# Ethylene_Sensor.net
KiCad netlist of a schematic drawn in Altium Designer
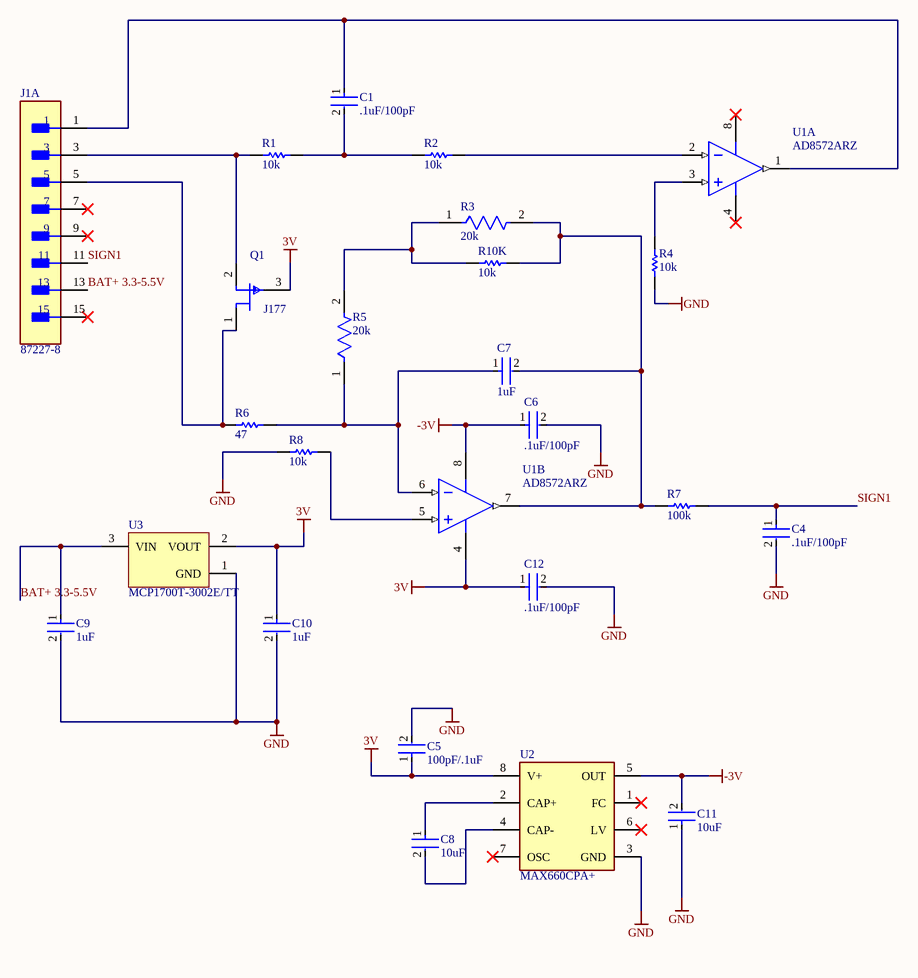
[diagram p0: Ethylene Sensor.SchDoc]

(export (version "E")
  (design (tool "Eeschema 10.0.6"))
  (components
    (comp (ref "C1")
      (value ".1uF/100pF")
      (footprint "FP-RCE0K1-MFG")
      (description "Cap Ceramic 100pF 100V C0G ±5% Radial 5mm +125°C Automotive Bulk")
      (fields (field (name "TOLERANCE") "5%"))
      (libsource (lib "Altium Content Vault") (part "b4654b650e69147ec39a6b967a45e02"))
    )
    (comp (ref "C4")
      (value ".1uF/100pF")
      (footprint "FP-RCE0K1-MFG")
      (description "Cap Ceramic 100pF 100V C0G ±5% Radial 5mm +125°C Automotive Bulk")
      (fields (field (name "TOLERANCE") "5%"))
      (libsource (lib "Altium Content Vault") (part "b4654b650e69147ec39a6b967a45e02"))
    )
    (comp (ref "C5")
      (value "100pF/.1uF")
      (footprint "FP-RCE0DB-MFG")
      (description "Cap Ceramic 100pF 100V C0G ±5% Radial 2.5mm +125°C Ammo Pack")
      (fields (field (name "TOLERANCE") "5%"))
      (libsource (lib "Altium Content Vault") (part "b4654b650e69147ec39a6b967a45e02"))
    )
    (comp (ref "C6")
      (value ".1uF/100pF")
      (footprint "FP-RCE0K1-MFG")
      (description "Cap Ceramic 100pF 100V C0G ±5% Radial 5mm +125°C Automotive Bulk")
      (fields (field (name "TOLERANCE") "5%"))
      (libsource (lib "Altium Content Vault") (part "b4654b650e69147ec39a6b967a45e02"))
    )
    (comp (ref "C7")
      (value "1uF")
      (footprint "FP-K105Z20Y5VF5TL2-MFG")
      (description "CAP CER 1UF 50V Y5V RADIAL")
      (fields
        (field (name "TOLERANCE") "-20+80%")
        (field (name "OCTOPART") "https://octopart.com/k105z20y5vf5tl2-vishay-39475252")
      )
      (libsource (lib "Altium Content Vault") (part "11868f565c42a9108669ba33697ecf6"))
    )
    (comp (ref "C8")
      (value "10uF")
      (footprint "FP-RCE3M1-MFG")
      (description "Cap Ceramic 10uF 25V X7R ±10% Radial 5mm +125°C Automotive Ammo Pack")
      (fields (field (name "TOLERANCE") "10%"))
      (libsource (lib "Altium Content Vault") (part "02cd4be3c70576c341d710602a673aa"))
    )
    (comp (ref "C9")
      (value "1uF")
      (footprint "FP-K105Z20Y5VF5TL2-MFG")
      (description "CAP CER 1UF 50V Y5V RADIAL")
      (fields
        (field (name "TOLERANCE") "-20+80%")
        (field (name "OCTOPART") "https://octopart.com/k105z20y5vf5tl2-vishay-39475252")
      )
      (libsource (lib "Altium Content Vault") (part "11868f565c42a9108669ba33697ecf6"))
    )
    (comp (ref "C10")
      (value "1uF")
      (footprint "FP-K105Z20Y5VF5TL2-MFG")
      (description "CAP CER 1UF 50V Y5V RADIAL")
      (fields
        (field (name "TOLERANCE") "-20+80%")
        (field (name "OCTOPART") "https://octopart.com/k105z20y5vf5tl2-vishay-39475252")
      )
      (libsource (lib "Altium Content Vault") (part "11868f565c42a9108669ba33697ecf6"))
    )
    (comp (ref "C11")
      (value "10uF")
      (footprint "FP-RCE3M1-MFG")
      (description "Cap Ceramic 10uF 25V X7R ±10% Radial 5mm +125°C Automotive Ammo Pack")
      (fields (field (name "TOLERANCE") "10%"))
      (libsource (lib "Altium Content Vault") (part "02cd4be3c70576c341d710602a673aa"))
    )
    (comp (ref "C12")
      (value ".1uF/100pF")
      (footprint "FP-RCE0K1-MFG")
      (description "Cap Ceramic 100pF 100V C0G ±5% Radial 5mm +125°C Automotive Bulk")
      (fields (field (name "TOLERANCE") "5%"))
      (libsource (lib "Altium Content Vault") (part "b4654b650e69147ec39a6b967a45e02"))
    )
    (comp (ref "J1")
      (value "87227-8")
      (footprint "FP-87227-8-MFG")
      (description "CONN HEADER VERT 16POS 2.54MM")
      (fields
        (field (name "MANUFACTURER") "TE Connectivity")
        (field (name "OCTOPART") "https://octopart.com/87227-8-te+connectivity-39407754")
      )
      (libsource (lib "Altium Content Vault") (part "4b6d22b45e2f925f038cba5d936fbcc"))
    )
    (comp (ref "Q1")
      (value "J177")
      (footprint "FP-318-08-IPC_C")
      (description "JFET P-CH 30V 0.225W SOT23")
      (libsource (lib "Altium Content Vault") (part "f35b6042eff1b6cb0a0a26375b7670e"))
    )
    (comp (ref "R1")
      (value "10k")
      (footprint "OMTE-RES7X2.5-2")
      (fields
        (field (name "TOLERANCE") "±5%")
        (field (name "PARTNUMBER") "OD103JE")
        (field (name "MANUFACTURER") "Ohmite")
      )
      (libsource (lib "Altium Content Vault") (part "RES-2"))
    )
    (comp (ref "R2")
      (value "10k")
      (footprint "OMTE-RES7X2.5-2")
      (fields
        (field (name "TOLERANCE") "±5%")
        (field (name "PARTNUMBER") "OD103JE")
        (field (name "MANUFACTURER") "Ohmite")
      )
      (libsource (lib "Altium Content Vault") (part "RES-2"))
    )
    (comp (ref "R3")
      (value "20k")
      (footprint "FP-S102K-MFG")
      (description "RES 20K OHM 0.6W 0.01% RADIAL")
      (fields (field (name "TOLERANCE") "0.01%"))
      (libsource (lib "Altium Content Vault") (part "1029c3af85768c4190bb7ad29bc67b5"))
    )
    (comp (ref "R4")
      (value "10k")
      (footprint "OMTE-RES7X2.5-2")
      (fields
        (field (name "TOLERANCE") "±5%")
        (field (name "PARTNUMBER") "OD103JE")
        (field (name "MANUFACTURER") "Ohmite")
      )
      (libsource (lib "Altium Content Vault") (part "RES-2"))
    )
    (comp (ref "R5")
      (value "20k")
      (footprint "FP-S102K-MFG")
      (description "RES 20K OHM 0.6W 0.01% RADIAL")
      (fields (field (name "TOLERANCE") "0.01%"))
      (libsource (lib "Altium Content Vault") (part "1029c3af85768c4190bb7ad29bc67b5"))
    )
    (comp (ref "R6")
      (value "47")
      (footprint "RESC1609X50X30LL10T20")
      (fields (field (name "MANUFACTURER") "Vishay Dale") (field (name "PART NUMBER") "CRCW060347R0FKEA"))
      (libsource (lib "Altium Content Vault") (part "RES"))
    )
    (comp (ref "R7")
      (value "100k")
      (footprint "RESA60-630X240")
      (description "Axial Resistor, 100 KOhm, +/- 1%, 0.25 W, -55 to 155 degC, 2-Pin THD, RoHS, Bulk")
      (fields (field (name "TOLERANCE") "1%"))
      (libsource (lib "Altium Content Vault") (part "RES-2"))
    )
    (comp (ref "R8")
      (value "10k")
      (footprint "OMTE-RES7X2.5-2")
      (fields
        (field (name "TOLERANCE") "±5%")
        (field (name "PARTNUMBER") "OD103JE")
        (field (name "MANUFACTURER") "Ohmite")
      )
      (libsource (lib "Altium Content Vault") (part "RES-2"))
    )
    (comp (ref "R10K")
      (value "10k")
      (footprint "OMTE-RES7X2.5-2")
      (fields
        (field (name "TOLERANCE") "±5%")
        (field (name "PARTNUMBER") "OD103JE")
        (field (name "MANUFACTURER") "Ohmite")
      )
      (libsource (lib "Altium Content Vault") (part "RES-2"))
    )
    (comp (ref "U1")
      (value "AD8572ARZ")
      (footprint "ADI-R-8_L")
      (fields (field (name "MANUFACTURER") "Analog Devices") (field (name "GENERIC PART NUMBER") "AD8572"))
      (libsource (lib "Altium Content Vault") (part "ADI-OP29X-R-8"))
    )
    (comp (ref "U2")
      (value "MAX660CPA+")
      (footprint "FP-P8-2-MFG")
      (description "IC REG CHARG PUMP INV 100MA 8DIP")
      (fields
        (field (name "OCTOPART") "https://octopart.com/max660cpa%2B-maxim+integrated-39427913")
        (field (name "MANUFACTURER") "Maxim Integrated")
      )
      (libsource (lib "Altium Content Vault") (part "cb4f88f8f8861f0afe4fdc40404f196"))
    )
    (comp (ref "U3")
      (value "MCP1700T-3002E/TT")
      (footprint "SOT-23-TT3_L")
      (description "Low Quiescent Current LDO, 3-Pin SOT-23, Extended Temperature, Tape and Reel")
      (libsource (lib "Altium Content Vault") (part "PM-LINEREG-MCP1700-IL3"))
    )
  )
  (nets
    (net (code "1") (name "-3V") (class "Default")
      (node (ref "C11") (pin "2") (pinfunction "2_2") (pintype "passive"))
      (node (ref "C6") (pin "1") (pinfunction "1_1") (pintype "passive"))
      (node (ref "U1") (pin "8") (pinfunction "+V_8") (pintype "power_in"))
      (node (ref "U2") (pin "5") (pinfunction "OUT_5") (pintype "power_in"))
    )
    (net (code "2") (name "/BAT+ 3.3-5.5V") (class "Default")
      (node (ref "C9") (pin "1") (pinfunction "1_1") (pintype "passive"))
      (node (ref "J1") (pin "13") (pinfunction "13_13") (pintype "passive"))
      (node (ref "U3") (pin "3") (pinfunction "VIN_3") (pintype "power_in"))
    )
    (net (code "3") (name "/SIGN1") (class "Default")
      (node (ref "C4") (pin "1") (pinfunction "1_1") (pintype "passive"))
      (node (ref "J1") (pin "11") (pinfunction "11_11") (pintype "passive"))
      (node (ref "R7") (pin "2") (pinfunction "2_2") (pintype "passive"))
    )
    (net (code "4") (name "3V") (class "Default")
      (node (ref "C10") (pin "1") (pinfunction "1_1") (pintype "passive"))
      (node (ref "C12") (pin "1") (pinfunction "1_1") (pintype "passive"))
      (node (ref "C5") (pin "1") (pinfunction "1_1") (pintype "passive"))
      (node (ref "Q1") (pin "3") (pinfunction "G_3") (pintype "passive"))
      (node (ref "U1") (pin "4") (pinfunction "-V_4") (pintype "power_in"))
      (node (ref "U2") (pin "8") (pinfunction "V+_8") (pintype "power_in"))
      (node (ref "U3") (pin "2") (pinfunction "VOUT_2") (pintype "power_in"))
    )
    (net (code "5") (name "GND") (class "Default")
      (node (ref "C10") (pin "2") (pinfunction "2_2") (pintype "passive"))
      (node (ref "C11") (pin "1") (pinfunction "1_1") (pintype "passive"))
      (node (ref "C12") (pin "2") (pinfunction "2_2") (pintype "passive"))
      (node (ref "C4") (pin "2") (pinfunction "2_2") (pintype "passive"))
      (node (ref "C5") (pin "2") (pinfunction "2_2") (pintype "passive"))
      (node (ref "C6") (pin "2") (pinfunction "2_2") (pintype "passive"))
      (node (ref "C9") (pin "2") (pinfunction "2_2") (pintype "passive"))
      (node (ref "R4") (pin "1") (pinfunction "1_1") (pintype "passive"))
      (node (ref "R8") (pin "1") (pinfunction "1_1") (pintype "passive"))
      (node (ref "U2") (pin "3") (pinfunction "GND_3") (pintype "power_in"))
      (node (ref "U3") (pin "1") (pinfunction "GND_1") (pintype "power_in"))
    )
    (net (code "6") (name "Net-(C1-Pad2)") (class "Default")
      (node (ref "C1") (pin "2") (pinfunction "2_2") (pintype "passive"))
      (node (ref "R1") (pin "2") (pinfunction "2_2") (pintype "passive"))
      (node (ref "R2") (pin "1") (pinfunction "1_1") (pintype "passive"))
    )
    (net (code "7") (name "Net-(Q1-D)") (class "Default")
      (node (ref "J1") (pin "5") (pinfunction "5_5") (pintype "passive"))
      (node (ref "Q1") (pin "1") (pinfunction "D_1") (pintype "passive"))
      (node (ref "R6") (pin "1") (pinfunction "1_1") (pintype "passive"))
    )
    (net (code "8") (name "Net-(Q1-S)") (class "Default")
      (node (ref "J1") (pin "3") (pinfunction "3_3") (pintype "passive"))
      (node (ref "Q1") (pin "2") (pinfunction "S_2") (pintype "passive"))
      (node (ref "R1") (pin "1") (pinfunction "1_1") (pintype "passive"))
    )
    (net (code "9") (name "Net-(R10K-Pad1)") (class "Default")
      (node (ref "R10K") (pin "1") (pinfunction "1_1") (pintype "passive"))
      (node (ref "R3") (pin "1") (pinfunction "1_1") (pintype "passive"))
      (node (ref "R5") (pin "2") (pinfunction "2_2") (pintype "passive"))
    )
    (net (code "10") (name "Net-(U1A-+IN_A)") (class "Default")
      (node (ref "R4") (pin "2") (pinfunction "2_2") (pintype "passive"))
      (node (ref "U1") (pin "3") (pinfunction "+IN_A_3") (pintype "input"))
    )
    (net (code "11") (name "Net-(U1A--IN_A)") (class "Default")
      (node (ref "R2") (pin "2") (pinfunction "2_2") (pintype "passive"))
      (node (ref "U1") (pin "2") (pinfunction "-IN_A_2") (pintype "input"))
    )
    (net (code "12") (name "Net-(U1A-OUT_A)") (class "Default")
      (node (ref "C1") (pin "1") (pinfunction "1_1") (pintype "passive"))
      (node (ref "J1") (pin "1") (pinfunction "1_1") (pintype "passive"))
      (node (ref "U1") (pin "1") (pinfunction "OUT_A_1") (pintype "output"))
    )
    (net (code "13") (name "Net-(U1B-+IN_B)") (class "Default")
      (node (ref "R8") (pin "2") (pinfunction "2_2") (pintype "passive"))
      (node (ref "U1") (pin "5") (pinfunction "+IN_B_5") (pintype "input"))
    )
    (net (code "14") (name "Net-(U1B--IN_B)") (class "Default")
      (node (ref "C7") (pin "1") (pinfunction "1_1") (pintype "passive"))
      (node (ref "R5") (pin "1") (pinfunction "1_1") (pintype "passive"))
      (node (ref "R6") (pin "2") (pinfunction "2_2") (pintype "passive"))
      (node (ref "U1") (pin "6") (pinfunction "-IN_B_6") (pintype "input"))
    )
    (net (code "15") (name "Net-(U1B-OUT_B)") (class "Default")
      (node (ref "C7") (pin "2") (pinfunction "2_2") (pintype "passive"))
      (node (ref "R10K") (pin "2") (pinfunction "2_2") (pintype "passive"))
      (node (ref "R3") (pin "2") (pinfunction "2_2") (pintype "passive"))
      (node (ref "R7") (pin "1") (pinfunction "1_1") (pintype "passive"))
      (node (ref "U1") (pin "7") (pinfunction "OUT_B_7") (pintype "output"))
    )
    (net (code "16") (name "Net-(U2-CAP+)") (class "Default")
      (node (ref "C8") (pin "1") (pinfunction "1_1") (pintype "passive"))
      (node (ref "U2") (pin "2") (pinfunction "CAP+_2") (pintype "passive"))
    )
    (net (code "17") (name "Net-(U2-CAP-)") (class "Default")
      (node (ref "C8") (pin "2") (pinfunction "2_2") (pintype "passive"))
      (node (ref "U2") (pin "4") (pinfunction "CAP-_4") (pintype "passive"))
    )
    (net (code "18") (name "unconnected-(J1-Pad7)") (class "Default")
      (node (ref "J1") (pin "7") (pinfunction "7_7") (pintype "passive+no_connect"))
    )
    (net (code "19") (name "unconnected-(J1-Pad9)") (class "Default")
      (node (ref "J1") (pin "9") (pinfunction "9_9") (pintype "passive+no_connect"))
    )
    (net (code "20") (name "unconnected-(J1-Pad15)") (class "Default")
      (node (ref "J1") (pin "15") (pinfunction "15_15") (pintype "passive+no_connect"))
    )
    (net (code "21") (name "unconnected-(U1A-+V-Pad8)") (class "Default")
      (node (ref "U1") (pin "8") (pinfunction "+V_8") (pintype "power_in+no_connect"))
    )
    (net (code "22") (name "unconnected-(U1A--V-Pad4)") (class "Default")
      (node (ref "U1") (pin "4") (pinfunction "-V_4") (pintype "power_in+no_connect"))
    )
    (net (code "23") (name "unconnected-(U2-FC-Pad1)") (class "Default")
      (node (ref "U2") (pin "1") (pinfunction "FC_1") (pintype "passive+no_connect"))
    )
    (net (code "24") (name "unconnected-(U2-LV-Pad6)") (class "Default")
      (node (ref "U2") (pin "6") (pinfunction "LV_6") (pintype "passive+no_connect"))
    )
    (net (code "25") (name "unconnected-(U2-OSC-Pad7)") (class "Default")
      (node (ref "U2") (pin "7") (pinfunction "OSC_7") (pintype "passive+no_connect"))
    )
  )
)
